# WS2811.net
KiCad netlist of a schematic drawn in Altium Designer
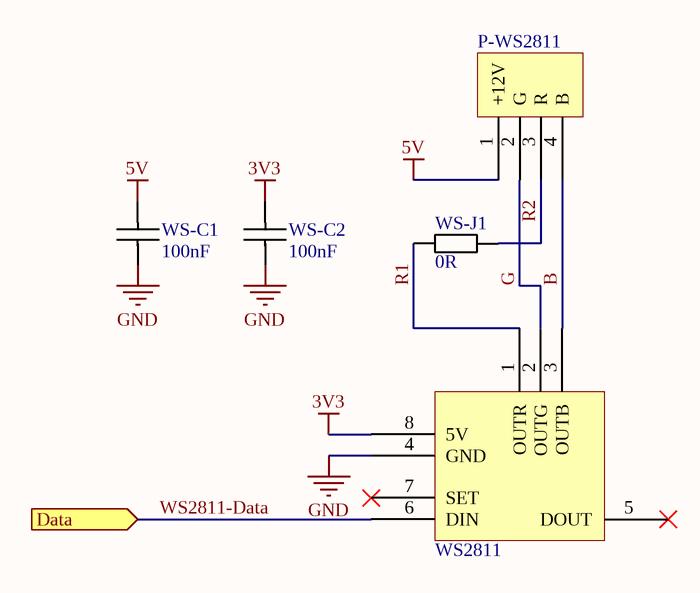
[diagram p0: WS2811.SchDoc]

(export (version "E")
  (design (tool "Eeschema 10.0.6"))
  (components
    (comp (ref "P-WS2811")
      (value "LED strip RGB")
      (footprint "LED strip RGB connector")
      (libsource (lib "Core51822-related") (part "LED strip RGB"))
    )
    (comp (ref "WS-C1")
      (value "100nF")
      (footprint "C 0805 / 2012")
      (libsource (lib "Standard") (part "Capacitor"))
    )
    (comp (ref "WS-C2")
      (value "100nF")
      (footprint "C 0805 / 2012")
      (libsource (lib "Standard") (part "Capacitor"))
    )
    (comp (ref "WS-J1")
      (value "0R")
      (footprint "R 0805 / 2012 wide")
      (libsource (lib "Standard") (part "Resistor"))
    )
    (comp (ref "WS2811")
      (value "WS2811S")
      (footprint "SOIC-8")
      (description "RGB LED Controller")
      (libsource (lib "ICs") (part "WS2811S"))
    )
  )
  (nets
    (net (code "1") (name "/B") (class "Default")
      (node (ref "P-WS2811") (pin "4") (pinfunction "B_4") (pintype "passive"))
      (node (ref "WS2811") (pin "3") (pinfunction "OUTB_3") (pintype "passive"))
    )
    (net (code "2") (name "/G") (class "Default")
      (node (ref "P-WS2811") (pin "2") (pinfunction "G_2") (pintype "passive"))
      (node (ref "WS2811") (pin "2") (pinfunction "OUTG_2") (pintype "passive"))
    )
    (net (code "3") (name "/R1") (class "Default")
      (node (ref "WS-J1") (pin "1") (pinfunction "1_1") (pintype "passive"))
      (node (ref "WS2811") (pin "1") (pinfunction "OUTR_1") (pintype "passive"))
    )
    (net (code "4") (name "/R2") (class "Default")
      (node (ref "P-WS2811") (pin "3") (pinfunction "R_3") (pintype "passive"))
      (node (ref "WS-J1") (pin "2") (pinfunction "2_2") (pintype "passive"))
    )
    (net (code "5") (name "/WS2811-Data") (class "Default")
      (node (ref "WS2811") (pin "6") (pinfunction "DIN_6") (pintype "passive"))
    )
    (net (code "6") (name "3V3") (class "Default")
      (node (ref "WS-C2") (pin "1") (pinfunction "1_1") (pintype "passive"))
      (node (ref "WS2811") (pin "8") (pinfunction "5V_8") (pintype "passive"))
    )
    (net (code "7") (name "5V") (class "Default")
      (node (ref "P-WS2811") (pin "1") (pinfunction "+12V_1") (pintype "passive"))
      (node (ref "WS-C1") (pin "1") (pinfunction "1_1") (pintype "passive"))
    )
    (net (code "8") (name "GND") (class "Default")
      (node (ref "WS-C1") (pin "2") (pinfunction "1_2") (pintype "passive"))
      (node (ref "WS-C2") (pin "2") (pinfunction "1_2") (pintype "passive"))
      (node (ref "WS2811") (pin "4") (pinfunction "GND_4") (pintype "passive"))
    )
    (net (code "9") (name "unconnected-(WS2811-DOUT-Pad5)") (class "Default")
      (node (ref "WS2811") (pin "5") (pinfunction "DOUT_5") (pintype "passive+no_connect"))
    )
    (net (code "10") (name "unconnected-(WS2811-SET-Pad7)") (class "Default")
      (node (ref "WS2811") (pin "7") (pinfunction "SET_7") (pintype "passive+no_connect"))
    )
  )
)
